# iqdemod.net
KiCad netlist of a schematic drawn in EAGLE
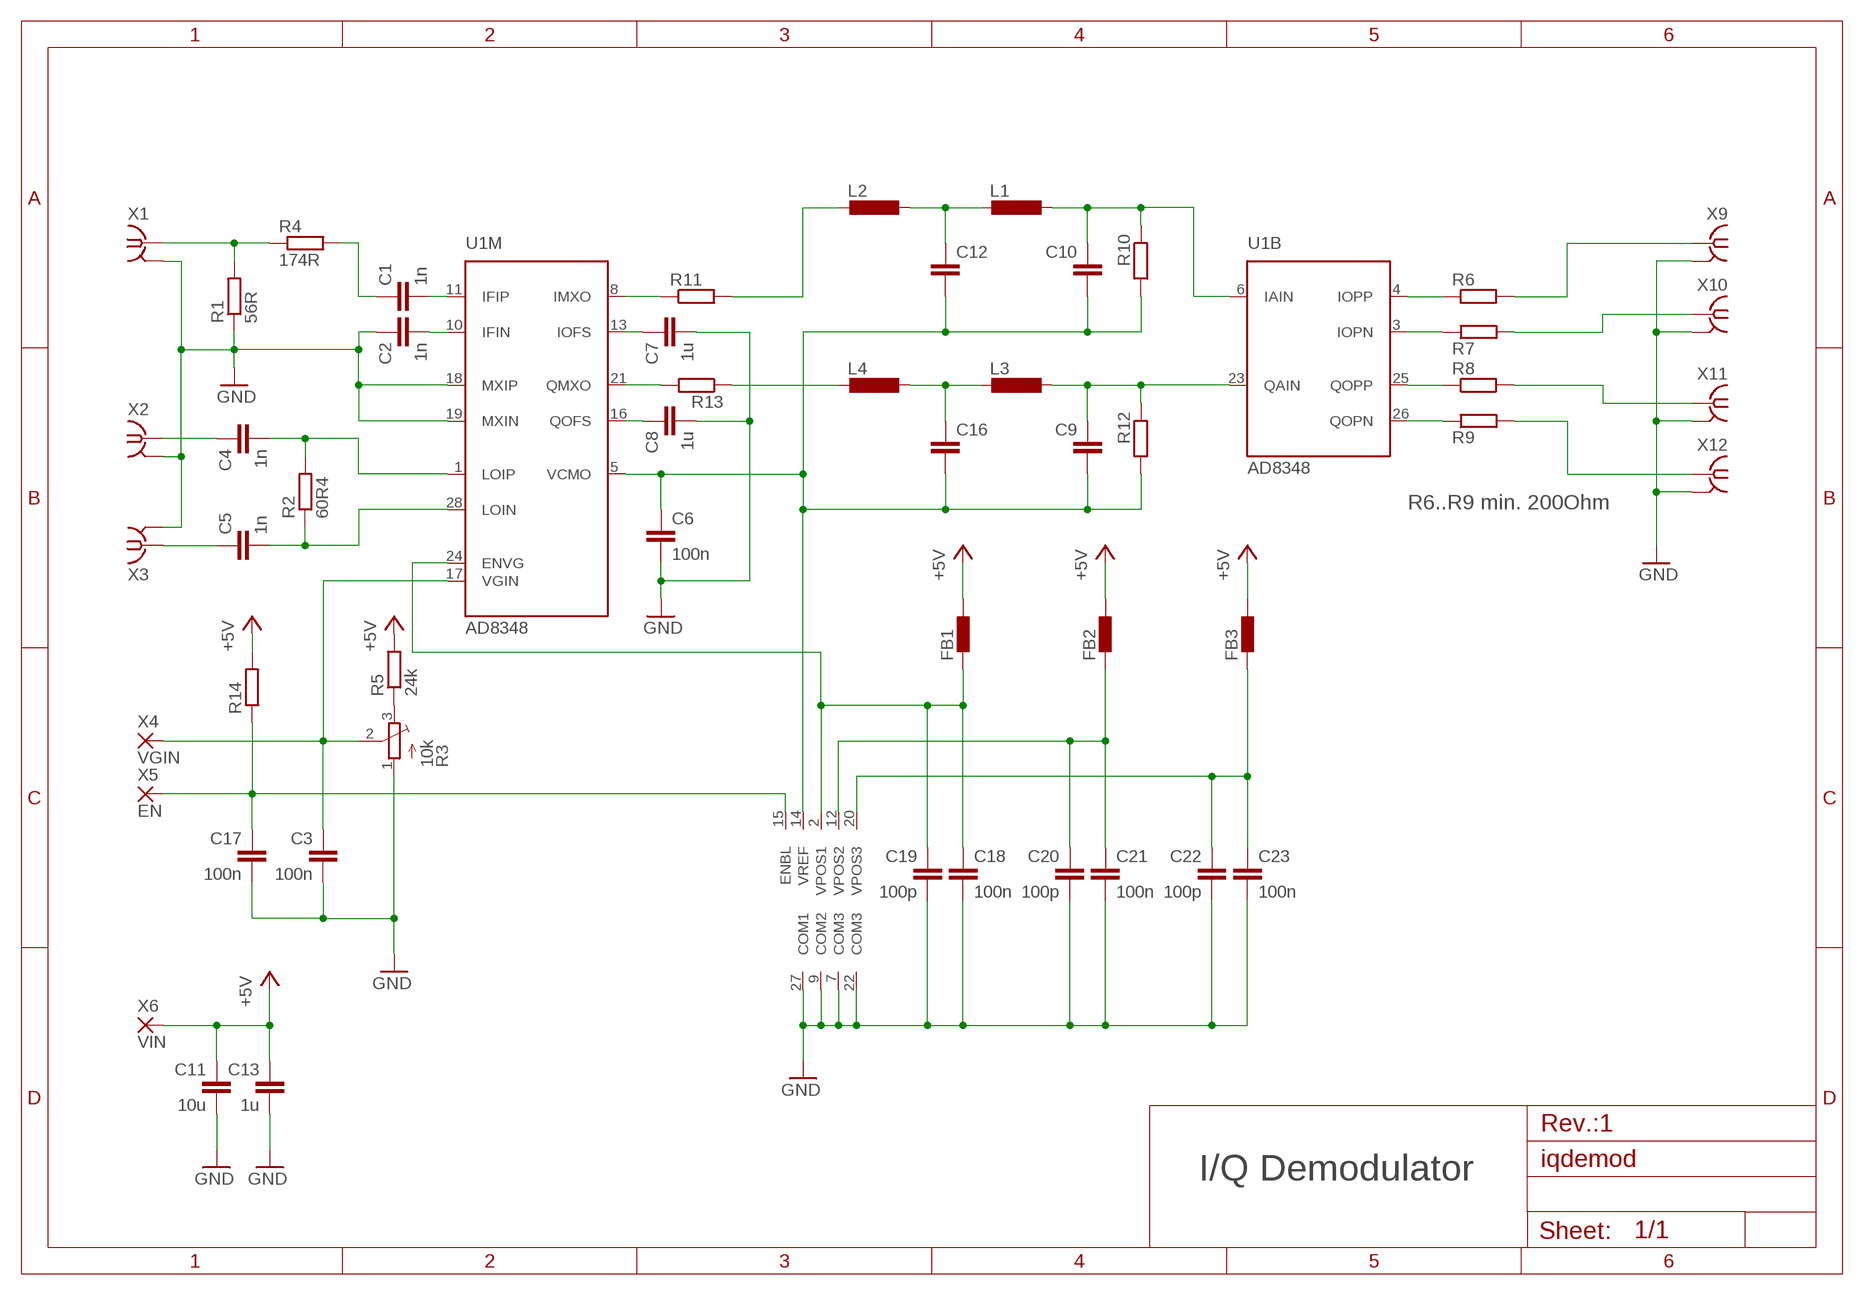
[diagram p0: schematic, sheet 1]

(export (version "E")
  (design (tool "Eeschema 10.0.6"))
  (components
    (comp (ref "C1")
      (value "1n")
      (footprint "eagle-import:C0603")
      (libsource (lib "eagle-import") (part "C-EUC0603"))
    )
    (comp (ref "C2")
      (value "1n")
      (footprint "eagle-import:C0603")
      (libsource (lib "eagle-import") (part "C-EUC0603"))
    )
    (comp (ref "C3")
      (value "100n")
      (footprint "eagle-import:C0603")
      (libsource (lib "eagle-import") (part "C-EUC0603"))
    )
    (comp (ref "C4")
      (value "1n")
      (footprint "eagle-import:C0603")
      (libsource (lib "eagle-import") (part "C-EUC0603"))
    )
    (comp (ref "C5")
      (value "1n")
      (footprint "eagle-import:C0603")
      (libsource (lib "eagle-import") (part "C-EUC0603"))
    )
    (comp (ref "C6")
      (value "100n")
      (footprint "eagle-import:C0603")
      (libsource (lib "eagle-import") (part "C-EUC0603"))
    )
    (comp (ref "C7")
      (value "1u")
      (footprint "eagle-import:C0603")
      (libsource (lib "eagle-import") (part "C-EUC0603"))
    )
    (comp (ref "C8")
      (value "1u")
      (footprint "eagle-import:C0603")
      (libsource (lib "eagle-import") (part "C-EUC0603"))
    )
    (comp (ref "C9")
      (value "C-EUC0603")
      (footprint "eagle-import:C0603")
      (libsource (lib "eagle-import") (part "C-EUC0603"))
    )
    (comp (ref "C10")
      (value "C-EUC0603")
      (footprint "eagle-import:C0603")
      (libsource (lib "eagle-import") (part "C-EUC0603"))
    )
    (comp (ref "C11")
      (value "10u")
      (footprint "eagle-import:C0603")
      (libsource (lib "eagle-import") (part "C-EUC0603"))
    )
    (comp (ref "C12")
      (value "C-EUC0603")
      (footprint "eagle-import:C0603")
      (libsource (lib "eagle-import") (part "C-EUC0603"))
    )
    (comp (ref "C13")
      (value "1u")
      (footprint "eagle-import:C0603")
      (libsource (lib "eagle-import") (part "C-EUC0603"))
    )
    (comp (ref "C16")
      (value "C-EUC0603")
      (footprint "eagle-import:C0603")
      (libsource (lib "eagle-import") (part "C-EUC0603"))
    )
    (comp (ref "C17")
      (value "100n")
      (footprint "eagle-import:C0603")
      (libsource (lib "eagle-import") (part "C-EUC0603"))
    )
    (comp (ref "C18")
      (value "100n")
      (footprint "eagle-import:C0603")
      (libsource (lib "eagle-import") (part "C-EUC0603"))
    )
    (comp (ref "C19")
      (value "100p")
      (footprint "eagle-import:C0603")
      (libsource (lib "eagle-import") (part "C-EUC0603"))
    )
    (comp (ref "C20")
      (value "100p")
      (footprint "eagle-import:C0603")
      (libsource (lib "eagle-import") (part "C-EUC0603"))
    )
    (comp (ref "C21")
      (value "100n")
      (footprint "eagle-import:C0603")
      (libsource (lib "eagle-import") (part "C-EUC0603"))
    )
    (comp (ref "C22")
      (value "100p")
      (footprint "eagle-import:C0603")
      (libsource (lib "eagle-import") (part "C-EUC0603"))
    )
    (comp (ref "C23")
      (value "100n")
      (footprint "eagle-import:C0603")
      (libsource (lib "eagle-import") (part "C-EUC0603"))
    )
    (comp (ref "FB1")
      (value "BML15H")
      (footprint "eagle-import:R0603")
      (libsource (lib "eagle-import") (part "BML15H"))
    )
    (comp (ref "FB2")
      (value "BML15H")
      (footprint "eagle-import:R0603")
      (libsource (lib "eagle-import") (part "BML15H"))
    )
    (comp (ref "FB3")
      (value "BML15H")
      (footprint "eagle-import:R0603")
      (libsource (lib "eagle-import") (part "BML15H"))
    )
    (comp (ref "L1")
      (value "L-EUL2012C")
      (footprint "eagle-import:L2012C")
      (libsource (lib "eagle-import") (part "L-EUL2012C"))
    )
    (comp (ref "L2")
      (value "L-EUL2012C")
      (footprint "eagle-import:L2012C")
      (libsource (lib "eagle-import") (part "L-EUL2012C"))
    )
    (comp (ref "L3")
      (value "L-EUL2012C")
      (footprint "eagle-import:L2012C")
      (libsource (lib "eagle-import") (part "L-EUL2012C"))
    )
    (comp (ref "L4")
      (value "L-EUL2012C")
      (footprint "eagle-import:L2012C")
      (libsource (lib "eagle-import") (part "L-EUL2012C"))
    )
    (comp (ref "R1")
      (value "56R")
      (footprint "eagle-import:R0603")
      (libsource (lib "eagle-import") (part "R-EU_R0603"))
    )
    (comp (ref "R2")
      (value "60R4")
      (footprint "eagle-import:R0603")
      (libsource (lib "eagle-import") (part "R-EU_R0603"))
    )
    (comp (ref "R3")
      (value "10k")
      (footprint "eagle-import:3223J")
      (libsource (lib "eagle-import") (part "TRIM_EU-3223J"))
    )
    (comp (ref "R4")
      (value "174R")
      (footprint "eagle-import:R0603")
      (libsource (lib "eagle-import") (part "R-EU_R0603"))
    )
    (comp (ref "R5")
      (value "24k")
      (footprint "eagle-import:R0603")
      (libsource (lib "eagle-import") (part "R-EU_R0603"))
    )
    (comp (ref "R6")
      (value "R-EU_R0603")
      (footprint "eagle-import:R0603")
      (libsource (lib "eagle-import") (part "R-EU_R0603"))
    )
    (comp (ref "R7")
      (value "R-EU_R0603")
      (footprint "eagle-import:R0603")
      (libsource (lib "eagle-import") (part "R-EU_R0603"))
    )
    (comp (ref "R8")
      (value "R-EU_R0603")
      (footprint "eagle-import:R0603")
      (libsource (lib "eagle-import") (part "R-EU_R0603"))
    )
    (comp (ref "R9")
      (value "R-EU_R0603")
      (footprint "eagle-import:R0603")
      (libsource (lib "eagle-import") (part "R-EU_R0603"))
    )
    (comp (ref "R10")
      (value "R-EU_R0603")
      (footprint "eagle-import:R0603")
      (libsource (lib "eagle-import") (part "R-EU_R0603"))
    )
    (comp (ref "R11")
      (value "R-EU_R0603")
      (footprint "eagle-import:R0603")
      (libsource (lib "eagle-import") (part "R-EU_R0603"))
    )
    (comp (ref "R12")
      (value "R-EU_R0603")
      (footprint "eagle-import:R0603")
      (libsource (lib "eagle-import") (part "R-EU_R0603"))
    )
    (comp (ref "R13")
      (value "R-EU_R0603")
      (footprint "eagle-import:R0603")
      (libsource (lib "eagle-import") (part "R-EU_R0603"))
    )
    (comp (ref "R14")
      (value "R-EU_R0603")
      (footprint "eagle-import:R0603")
      (libsource (lib "eagle-import") (part "R-EU_R0603"))
    )
    (comp (ref "U1")
      (value "AD8348")
      (footprint "eagle-import:TSSOP28")
      (libsource (lib "eagle-import") (part "AD8348"))
    )
    (comp (ref "X1")
      (value "SMA-142-0701-881/886")
      (footprint "eagle-import:J502-ND-142-0701-881_886")
      (fields (field (name "MF") "JOHNSON COMPONENTS") (field (name "MPN") "142-0701-881"))
      (libsource (lib "eagle-import") (part "SMA-142-0701-881/886"))
    )
    (comp (ref "X2")
      (value "SMA-142-0701-881/886")
      (footprint "eagle-import:J502-ND-142-0701-881_886")
      (fields (field (name "MF") "JOHNSON COMPONENTS") (field (name "MPN") "142-0701-881"))
      (libsource (lib "eagle-import") (part "SMA-142-0701-881/886"))
    )
    (comp (ref "X3")
      (value "SMA-142-0701-881/886")
      (footprint "eagle-import:J502-ND-142-0701-881_886")
      (fields (field (name "MF") "JOHNSON COMPONENTS") (field (name "MPN") "142-0701-881"))
      (libsource (lib "eagle-import") (part "SMA-142-0701-881/886"))
    )
    (comp (ref "X4")
      (value "VGIN")
      (footprint "eagle-import:SMD1,27-2,54")
      (libsource (lib "eagle-import") (part "SMD2"))
    )
    (comp (ref "X5")
      (value "EN")
      (footprint "eagle-import:SMD1,27-2,54")
      (libsource (lib "eagle-import") (part "SMD2"))
    )
    (comp (ref "X6")
      (value "VIN")
      (footprint "eagle-import:SMD1,27-2,54")
      (libsource (lib "eagle-import") (part "SMD2"))
    )
    (comp (ref "X9")
      (value "SMA-142-0701-881/886")
      (footprint "eagle-import:J502-ND-142-0701-881_886")
      (fields (field (name "MF") "JOHNSON COMPONENTS") (field (name "MPN") "142-0701-881"))
      (libsource (lib "eagle-import") (part "SMA-142-0701-881/886"))
    )
    (comp (ref "X10")
      (value "SMA-142-0701-881/886")
      (footprint "eagle-import:J502-ND-142-0701-881_886")
      (fields (field (name "MF") "JOHNSON COMPONENTS") (field (name "MPN") "142-0701-881"))
      (libsource (lib "eagle-import") (part "SMA-142-0701-881/886"))
    )
    (comp (ref "X11")
      (value "SMA-142-0701-881/886")
      (footprint "eagle-import:J502-ND-142-0701-881_886")
      (fields (field (name "MF") "JOHNSON COMPONENTS") (field (name "MPN") "142-0701-881"))
      (libsource (lib "eagle-import") (part "SMA-142-0701-881/886"))
    )
    (comp (ref "X12")
      (value "SMA-142-0701-881/886")
      (footprint "eagle-import:J502-ND-142-0701-881_886")
      (fields (field (name "MF") "JOHNSON COMPONENTS") (field (name "MPN") "142-0701-881"))
      (libsource (lib "eagle-import") (part "SMA-142-0701-881/886"))
    )
  )
  (nets
    (net (code "1") (name "+5V") (class "Default")
      (node (ref "C11") (pin "1") (pinfunction "1_1") (pintype "passive"))
      (node (ref "C13") (pin "1") (pinfunction "1_1") (pintype "passive"))
      (node (ref "FB1") (pin "2") (pinfunction "2_2") (pintype "passive"))
      (node (ref "FB2") (pin "2") (pinfunction "2_2") (pintype "passive"))
      (node (ref "FB3") (pin "2") (pinfunction "2_2") (pintype "passive"))
      (node (ref "R14") (pin "2") (pinfunction "2_2") (pintype "passive"))
      (node (ref "R5") (pin "2") (pinfunction "2_2") (pintype "passive"))
      (node (ref "X6") (pin "1") (pinfunction "P_1") (pintype "passive"))
    )
    (net (code "2") (name "GND") (class "Default")
      (node (ref "C11") (pin "2") (pinfunction "2_2") (pintype "passive"))
      (node (ref "C13") (pin "2") (pinfunction "2_2") (pintype "passive"))
      (node (ref "C17") (pin "2") (pinfunction "2_2") (pintype "passive"))
      (node (ref "C18") (pin "2") (pinfunction "2_2") (pintype "passive"))
      (node (ref "C19") (pin "2") (pinfunction "2_2") (pintype "passive"))
      (node (ref "C2") (pin "1") (pinfunction "1_1") (pintype "passive"))
      (node (ref "C20") (pin "2") (pinfunction "2_2") (pintype "passive"))
      (node (ref "C21") (pin "2") (pinfunction "2_2") (pintype "passive"))
      (node (ref "C22") (pin "2") (pinfunction "2_2") (pintype "passive"))
      (node (ref "C23") (pin "2") (pinfunction "2_2") (pintype "passive"))
      (node (ref "C3") (pin "2") (pinfunction "2_2") (pintype "passive"))
      (node (ref "C6") (pin "2") (pinfunction "2_2") (pintype "passive"))
      (node (ref "C7") (pin "2") (pinfunction "2_2") (pintype "passive"))
      (node (ref "C8") (pin "2") (pinfunction "2_2") (pintype "passive"))
      (node (ref "R1") (pin "1") (pinfunction "1_1") (pintype "passive"))
      (node (ref "R3") (pin "1") (pinfunction "A_1") (pintype "passive"))
      (node (ref "U1") (pin "18") (pinfunction "MXIP_18") (pintype "input"))
      (node (ref "U1") (pin "19") (pinfunction "MXIN_19") (pintype "input"))
      (node (ref "U1") (pin "22") (pinfunction "COM3_22") (pintype "power_in"))
      (node (ref "U1") (pin "27") (pinfunction "COM1_27") (pintype "power_in"))
      (node (ref "U1") (pin "7") (pinfunction "COM3_7") (pintype "power_in"))
      (node (ref "U1") (pin "9") (pinfunction "COM2_9") (pintype "power_in"))
      (node (ref "X1") (pin "G@1") (pinfunction "2_G@1") (pintype "passive"))
      (node (ref "X1") (pin "G@2") (pinfunction "2_G@2") (pintype "passive"))
      (node (ref "X1") (pin "G@3") (pinfunction "2_G@3") (pintype "passive"))
      (node (ref "X1") (pin "G@4") (pinfunction "2_G@4") (pintype "passive"))
      (node (ref "X10") (pin "G@1") (pinfunction "2_G@1") (pintype "passive"))
      (node (ref "X10") (pin "G@2") (pinfunction "2_G@2") (pintype "passive"))
      (node (ref "X10") (pin "G@3") (pinfunction "2_G@3") (pintype "passive"))
      (node (ref "X10") (pin "G@4") (pinfunction "2_G@4") (pintype "passive"))
      (node (ref "X11") (pin "G@1") (pinfunction "2_G@1") (pintype "passive"))
      (node (ref "X11") (pin "G@2") (pinfunction "2_G@2") (pintype "passive"))
      (node (ref "X11") (pin "G@3") (pinfunction "2_G@3") (pintype "passive"))
      (node (ref "X11") (pin "G@4") (pinfunction "2_G@4") (pintype "passive"))
      (node (ref "X12") (pin "G@1") (pinfunction "2_G@1") (pintype "passive"))
      (node (ref "X12") (pin "G@2") (pinfunction "2_G@2") (pintype "passive"))
      (node (ref "X12") (pin "G@3") (pinfunction "2_G@3") (pintype "passive"))
      (node (ref "X12") (pin "G@4") (pinfunction "2_G@4") (pintype "passive"))
      (node (ref "X2") (pin "G@1") (pinfunction "2_G@1") (pintype "passive"))
      (node (ref "X2") (pin "G@2") (pinfunction "2_G@2") (pintype "passive"))
      (node (ref "X2") (pin "G@3") (pinfunction "2_G@3") (pintype "passive"))
      (node (ref "X2") (pin "G@4") (pinfunction "2_G@4") (pintype "passive"))
      (node (ref "X3") (pin "G@1") (pinfunction "2_G@1") (pintype "passive"))
      (node (ref "X3") (pin "G@2") (pinfunction "2_G@2") (pintype "passive"))
      (node (ref "X3") (pin "G@3") (pinfunction "2_G@3") (pintype "passive"))
      (node (ref "X3") (pin "G@4") (pinfunction "2_G@4") (pintype "passive"))
      (node (ref "X9") (pin "G@1") (pinfunction "2_G@1") (pintype "passive"))
      (node (ref "X9") (pin "G@2") (pinfunction "2_G@2") (pintype "passive"))
      (node (ref "X9") (pin "G@3") (pinfunction "2_G@3") (pintype "passive"))
      (node (ref "X9") (pin "G@4") (pinfunction "2_G@4") (pintype "passive"))
    )
    (net (code "3") (name "Net-(C1-Pad1)") (class "Default")
      (node (ref "C1") (pin "1") (pinfunction "1_1") (pintype "passive"))
      (node (ref "R4") (pin "2") (pinfunction "2_2") (pintype "passive"))
    )
    (net (code "4") (name "Net-(C4-Pad1)") (class "Default")
      (node (ref "C4") (pin "1") (pinfunction "1_1") (pintype "passive"))
      (node (ref "X2") (pin "1") (pinfunction "1_1") (pintype "passive"))
    )
    (net (code "5") (name "Net-(C5-Pad1)") (class "Default")
      (node (ref "C5") (pin "1") (pinfunction "1_1") (pintype "passive"))
      (node (ref "X3") (pin "1") (pinfunction "1_1") (pintype "passive"))
    )
    (net (code "6") (name "Net-(C12-Pad1)") (class "Default")
      (node (ref "C12") (pin "1") (pinfunction "1_1") (pintype "passive"))
      (node (ref "L1") (pin "2") (pinfunction "2_2") (pintype "passive"))
      (node (ref "L2") (pin "1") (pinfunction "1_1") (pintype "passive"))
    )
    (net (code "7") (name "Net-(C16-Pad1)") (class "Default")
      (node (ref "C16") (pin "1") (pinfunction "1_1") (pintype "passive"))
      (node (ref "L3") (pin "2") (pinfunction "2_2") (pintype "passive"))
      (node (ref "L4") (pin "1") (pinfunction "1_1") (pintype "passive"))
    )
    (net (code "8") (name "Net-(L2-Pad2)") (class "Default")
      (node (ref "L2") (pin "2") (pinfunction "2_2") (pintype "passive"))
      (node (ref "R11") (pin "2") (pinfunction "2_2") (pintype "passive"))
    )
    (net (code "9") (name "Net-(L4-Pad2)") (class "Default")
      (node (ref "L4") (pin "2") (pinfunction "2_2") (pintype "passive"))
      (node (ref "R13") (pin "1") (pinfunction "1_1") (pintype "passive"))
    )
    (net (code "10") (name "Net-(R1-Pad2)") (class "Default")
      (node (ref "R1") (pin "2") (pinfunction "2_2") (pintype "passive"))
      (node (ref "R4") (pin "1") (pinfunction "1_1") (pintype "passive"))
      (node (ref "X1") (pin "1") (pinfunction "1_1") (pintype "passive"))
    )
    (net (code "11") (name "Net-(R3-E)") (class "Default")
      (node (ref "R3") (pin "3") (pinfunction "E_3") (pintype "passive"))
      (node (ref "R5") (pin "1") (pinfunction "1_1") (pintype "passive"))
    )
    (net (code "12") (name "Net-(R3-S)") (class "Default")
      (node (ref "C3") (pin "1") (pinfunction "1_1") (pintype "passive"))
      (node (ref "R3") (pin "2") (pinfunction "S_2") (pintype "passive"))
      (node (ref "U1") (pin "17") (pinfunction "VGIN_17") (pintype "input"))
      (node (ref "X4") (pin "1") (pinfunction "P_1") (pintype "passive"))
    )
    (net (code "13") (name "Net-(R6-Pad2)") (class "Default")
      (node (ref "R6") (pin "2") (pinfunction "2_2") (pintype "passive"))
      (node (ref "X9") (pin "1") (pinfunction "1_1") (pintype "passive"))
    )
    (net (code "14") (name "Net-(R7-Pad2)") (class "Default")
      (node (ref "R7") (pin "2") (pinfunction "2_2") (pintype "passive"))
      (node (ref "X10") (pin "1") (pinfunction "1_1") (pintype "passive"))
    )
    (net (code "15") (name "Net-(R8-Pad2)") (class "Default")
      (node (ref "R8") (pin "2") (pinfunction "2_2") (pintype "passive"))
      (node (ref "X11") (pin "1") (pinfunction "1_1") (pintype "passive"))
    )
    (net (code "16") (name "Net-(R9-Pad2)") (class "Default")
      (node (ref "R9") (pin "2") (pinfunction "2_2") (pintype "passive"))
      (node (ref "X12") (pin "1") (pinfunction "1_1") (pintype "passive"))
    )
    (net (code "17") (name "Net-(U1A-IAIN)") (class "Default")
      (node (ref "C10") (pin "1") (pinfunction "1_1") (pintype "passive"))
      (node (ref "L1") (pin "1") (pinfunction "1_1") (pintype "passive"))
      (node (ref "R10") (pin "1") (pinfunction "1_1") (pintype "passive"))
      (node (ref "U1") (pin "6") (pinfunction "IAIN_6") (pintype "input"))
    )
    (net (code "18") (name "Net-(U1A-IOPN)") (class "Default")
      (node (ref "R7") (pin "1") (pinfunction "1_1") (pintype "passive"))
      (node (ref "U1") (pin "3") (pinfunction "IOPN_3") (pintype "output"))
    )
    (net (code "19") (name "Net-(U1A-IOPP)") (class "Default")
      (node (ref "R6") (pin "1") (pinfunction "1_1") (pintype "passive"))
      (node (ref "U1") (pin "4") (pinfunction "IOPP_4") (pintype "output"))
    )
    (net (code "20") (name "Net-(U1A-QAIN)") (class "Default")
      (node (ref "C9") (pin "1") (pinfunction "1_1") (pintype "passive"))
      (node (ref "L3") (pin "1") (pinfunction "1_1") (pintype "passive"))
      (node (ref "R12") (pin "1") (pinfunction "1_1") (pintype "passive"))
      (node (ref "U1") (pin "23") (pinfunction "QAIN_23") (pintype "input"))
    )
    (net (code "21") (name "Net-(U1A-QOPN)") (class "Default")
      (node (ref "R9") (pin "1") (pinfunction "1_1") (pintype "passive"))
      (node (ref "U1") (pin "26") (pinfunction "QOPN_26") (pintype "output"))
    )
    (net (code "22") (name "Net-(U1A-QOPP)") (class "Default")
      (node (ref "R8") (pin "1") (pinfunction "1_1") (pintype "passive"))
      (node (ref "U1") (pin "25") (pinfunction "QOPP_25") (pintype "output"))
    )
    (net (code "23") (name "Net-(U1B-ENVG)") (class "Default")
      (node (ref "C18") (pin "1") (pinfunction "1_1") (pintype "passive"))
      (node (ref "C19") (pin "1") (pinfunction "1_1") (pintype "passive"))
      (node (ref "FB1") (pin "1") (pinfunction "1_1") (pintype "passive"))
      (node (ref "U1") (pin "2") (pinfunction "VPOS1_2") (pintype "power_in"))
      (node (ref "U1") (pin "24") (pinfunction "ENVG_24") (pintype "input"))
    )
    (net (code "24") (name "Net-(U1B-IFIN)") (class "Default")
      (node (ref "C2") (pin "2") (pinfunction "2_2") (pintype "passive"))
      (node (ref "U1") (pin "10") (pinfunction "IFIN_10") (pintype "input"))
    )
    (net (code "25") (name "Net-(U1B-IFIP)") (class "Default")
      (node (ref "C1") (pin "2") (pinfunction "2_2") (pintype "passive"))
      (node (ref "U1") (pin "11") (pinfunction "IFIP_11") (pintype "input"))
    )
    (net (code "26") (name "Net-(U1B-IMXO)") (class "Default")
      (node (ref "R11") (pin "1") (pinfunction "1_1") (pintype "passive"))
      (node (ref "U1") (pin "8") (pinfunction "IMXO_8") (pintype "output"))
    )
    (net (code "27") (name "Net-(U1B-IOFS)") (class "Default")
      (node (ref "C7") (pin "1") (pinfunction "1_1") (pintype "passive"))
      (node (ref "U1") (pin "13") (pinfunction "IOFS_13") (pintype "input"))
    )
    (net (code "28") (name "Net-(U1B-LOIN)") (class "Default")
      (node (ref "C5") (pin "2") (pinfunction "2_2") (pintype "passive"))
      (node (ref "R2") (pin "1") (pinfunction "1_1") (pintype "passive"))
      (node (ref "U1") (pin "28") (pinfunction "LOIN_28") (pintype "input"))
    )
    (net (code "29") (name "Net-(U1B-LOIP)") (class "Default")
      (node (ref "C4") (pin "2") (pinfunction "2_2") (pintype "passive"))
      (node (ref "R2") (pin "2") (pinfunction "2_2") (pintype "passive"))
      (node (ref "U1") (pin "1") (pinfunction "LOIP_1") (pintype "input"))
    )
    (net (code "30") (name "Net-(U1B-QMXO)") (class "Default")
      (node (ref "R13") (pin "2") (pinfunction "2_2") (pintype "passive"))
      (node (ref "U1") (pin "21") (pinfunction "QMXO_21") (pintype "output"))
    )
    (net (code "31") (name "Net-(U1B-QOFS)") (class "Default")
      (node (ref "C8") (pin "1") (pinfunction "1_1") (pintype "passive"))
      (node (ref "U1") (pin "16") (pinfunction "QOFS_16") (pintype "input"))
    )
    (net (code "32") (name "Net-(U1B-VCMO)") (class "Default")
      (node (ref "C10") (pin "2") (pinfunction "2_2") (pintype "passive"))
      (node (ref "C12") (pin "2") (pinfunction "2_2") (pintype "passive"))
      (node (ref "C16") (pin "2") (pinfunction "2_2") (pintype "passive"))
      (node (ref "C6") (pin "1") (pinfunction "1_1") (pintype "passive"))
      (node (ref "C9") (pin "2") (pinfunction "2_2") (pintype "passive"))
      (node (ref "R10") (pin "2") (pinfunction "2_2") (pintype "passive"))
      (node (ref "R12") (pin "2") (pinfunction "2_2") (pintype "passive"))
      (node (ref "U1") (pin "14") (pinfunction "VREF_14") (pintype "power_in"))
      (node (ref "U1") (pin "5") (pinfunction "VCMO_5") (pintype "input"))
    )
    (net (code "33") (name "Net-(U1C-ENBL)") (class "Default")
      (node (ref "C17") (pin "1") (pinfunction "1_1") (pintype "passive"))
      (node (ref "R14") (pin "1") (pinfunction "1_1") (pintype "passive"))
      (node (ref "U1") (pin "15") (pinfunction "ENBL_15") (pintype "power_in"))
      (node (ref "X5") (pin "1") (pinfunction "P_1") (pintype "passive"))
    )
    (net (code "34") (name "Net-(U1C-VPOS2)") (class "Default")
      (node (ref "C20") (pin "1") (pinfunction "1_1") (pintype "passive"))
      (node (ref "C21") (pin "1") (pinfunction "1_1") (pintype "passive"))
      (node (ref "FB2") (pin "1") (pinfunction "1_1") (pintype "passive"))
      (node (ref "U1") (pin "12") (pinfunction "VPOS2_12") (pintype "power_in"))
    )
    (net (code "35") (name "Net-(U1C-VPOS3)") (class "Default")
      (node (ref "C22") (pin "1") (pinfunction "1_1") (pintype "passive"))
      (node (ref "C23") (pin "1") (pinfunction "1_1") (pintype "passive"))
      (node (ref "FB3") (pin "1") (pinfunction "1_1") (pintype "passive"))
      (node (ref "U1") (pin "20") (pinfunction "VPOS3_20") (pintype "power_in"))
    )
  )
)
